# Superbot_motor_boost_mk2.net
KiCad netlist of a schematic drawn in Altium Designer
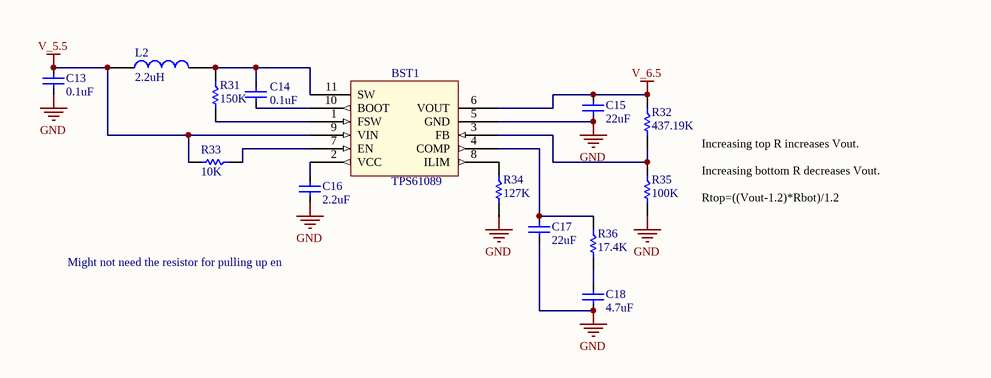
[diagram p0: Superbot_motor_boost_mk2.SchDoc]

(export (version "E")
  (design (tool "Eeschema 10.0.6"))
  (components
    (comp (ref "BST1")
      (value "TPS61089")
      (footprint "VQFN_RNR0011A_1mm")
      (description "Boost Switching Regulator IC Positive Adjustable 4.5V 1 Output 7A 11-VFQFN")
      (fields
        (field (name "MANUFACTURER") "Texas Instruments")
        (field (name "MANUFACTURER PART NUM") "TPS61089RNRT")
      )
      (libsource (lib "SuperBot_Schlib1") (part "TPS61089"))
    )
    (comp (ref "C13")
      (value "0.1uF")
      (footprint "CAP0603R")
      (description "Capacitor")
      (fields
        (field (name "MANUFACTURER") "Microchip Technology")
        (field (name "MANUFACTURER PART NUM") "MIC5378YC5-TR")
      )
      (libsource (lib "SuperBot_Schlib1") (part "C"))
    )
    (comp (ref "C14")
      (value "0.1uF")
      (footprint "CAP0603R")
      (description "Capacitor")
      (fields
        (field (name "MANUFACTURER") "Microchip Technology")
        (field (name "MANUFACTURER PART NUM") "MIC5378YC5-TR")
      )
      (libsource (lib "SuperBot_Schlib1") (part "C"))
    )
    (comp (ref "C15")
      (value "22uF")
      (footprint "CAP0805R")
      (description "Capacitor")
      (fields
        (field (name "MANUFACTURER") "Microchip Technology")
        (field (name "MANUFACTURER PART NUM") "MIC5378YC5-TR")
      )
      (libsource (lib "SuperBot_Schlib1") (part "C"))
    )
    (comp (ref "C16")
      (value "2.2uF")
      (footprint "CAP0603R")
      (description "Capacitor")
      (fields
        (field (name "MANUFACTURER") "Microchip Technology")
        (field (name "MANUFACTURER PART NUM") "MIC5378YC5-TR")
      )
      (libsource (lib "SuperBot_Schlib1") (part "C"))
    )
    (comp (ref "C17")
      (value "22uF")
      (footprint "CAP0805R")
      (description "Capacitor")
      (fields
        (field (name "MANUFACTURER") "Microchip Technology")
        (field (name "MANUFACTURER PART NUM") "MIC5378YC5-TR")
      )
      (libsource (lib "SuperBot_Schlib1") (part "C"))
    )
    (comp (ref "C18")
      (value "4.7uF")
      (footprint "CAP0603R")
      (description "Capacitor")
      (fields
        (field (name "MANUFACTURER") "Microchip Technology")
        (field (name "MANUFACTURER PART NUM") "MIC5378YC5-TR")
      )
      (libsource (lib "SuperBot_Schlib1") (part "C"))
    )
    (comp (ref "L2")
      (value "2.2uH")
      (footprint "744031004")
      (description "Inductor")
      (libsource (lib "SuperBot_Schlib1") (part "L"))
    )
    (comp (ref "R31")
      (value "150K")
      (footprint "RES0603R")
      (description "Resistor")
      (libsource (lib "SuperBot_Schlib1") (part "R"))
    )
    (comp (ref "R32")
      (value "437.19K")
      (footprint "RES0603R")
      (description "Resistor")
      (libsource (lib "SuperBot_Schlib1") (part "R"))
    )
    (comp (ref "R33")
      (value "10K")
      (footprint "RES0603R")
      (description "Resistor")
      (libsource (lib "SuperBot_Schlib1") (part "R"))
    )
    (comp (ref "R34")
      (value "127K")
      (footprint "RES0603R")
      (description "Resistor")
      (libsource (lib "SuperBot_Schlib1") (part "R"))
    )
    (comp (ref "R35")
      (value "100K")
      (footprint "RES0603R")
      (description "Resistor")
      (libsource (lib "SuperBot_Schlib1") (part "R"))
    )
    (comp (ref "R36")
      (value "17.4K")
      (footprint "RES0603R")
      (description "Resistor")
      (libsource (lib "SuperBot_Schlib1") (part "R"))
    )
  )
  (nets
    (net (code "1") (name "GND") (class "Default")
      (node (ref "BST1") (pin "5") (pinfunction "GND_5") (pintype "power_in"))
      (node (ref "C13") (pin "2") (pinfunction "2_2") (pintype "passive"))
      (node (ref "C15") (pin "2") (pinfunction "2_2") (pintype "passive"))
      (node (ref "C16") (pin "2") (pinfunction "2_2") (pintype "passive"))
      (node (ref "C17") (pin "2") (pinfunction "2_2") (pintype "passive"))
      (node (ref "C18") (pin "2") (pinfunction "2_2") (pintype "passive"))
      (node (ref "R34") (pin "2") (pintype "passive"))
      (node (ref "R35") (pin "2") (pintype "passive"))
    )
    (net (code "2") (name "Net-(BST1-BOOT)") (class "Default")
      (node (ref "BST1") (pin "10") (pinfunction "BOOT_10") (pintype "output"))
      (node (ref "C14") (pin "2") (pinfunction "2_2") (pintype "passive"))
    )
    (net (code "3") (name "Net-(BST1-COMP)") (class "Default")
      (node (ref "BST1") (pin "4") (pinfunction "COMP_4") (pintype "output"))
      (node (ref "C17") (pin "1") (pinfunction "1_1") (pintype "passive"))
      (node (ref "R36") (pin "1") (pintype "passive"))
    )
    (net (code "4") (name "Net-(BST1-EN)") (class "Default")
      (node (ref "BST1") (pin "7") (pinfunction "EN_7") (pintype "input"))
      (node (ref "R33") (pin "1") (pintype "passive"))
    )
    (net (code "5") (name "Net-(BST1-FB)") (class "Default")
      (node (ref "BST1") (pin "3") (pinfunction "FB_3") (pintype "input"))
      (node (ref "R32") (pin "2") (pintype "passive"))
      (node (ref "R35") (pin "1") (pintype "passive"))
    )
    (net (code "6") (name "Net-(BST1-FSW)") (class "Default")
      (node (ref "BST1") (pin "1") (pinfunction "FSW_1") (pintype "input"))
      (node (ref "R31") (pin "2") (pintype "passive"))
    )
    (net (code "7") (name "Net-(BST1-ILIM)") (class "Default")
      (node (ref "BST1") (pin "8") (pinfunction "ILIM_8") (pintype "output"))
      (node (ref "R34") (pin "1") (pintype "passive"))
    )
    (net (code "8") (name "Net-(BST1-SW)") (class "Default")
      (node (ref "BST1") (pin "11") (pinfunction "SW_11") (pintype "power_in"))
      (node (ref "C14") (pin "1") (pinfunction "1_1") (pintype "passive"))
      (node (ref "L2") (pin "2") (pinfunction "2_2") (pintype "passive"))
      (node (ref "R31") (pin "1") (pintype "passive"))
    )
    (net (code "9") (name "Net-(BST1-VCC)") (class "Default")
      (node (ref "BST1") (pin "2") (pinfunction "VCC_2") (pintype "output"))
      (node (ref "C16") (pin "1") (pinfunction "1_1") (pintype "passive"))
    )
    (net (code "10") (name "Net-(C18-Pad1)") (class "Default")
      (node (ref "C18") (pin "1") (pinfunction "1_1") (pintype "passive"))
      (node (ref "R36") (pin "2") (pintype "passive"))
    )
    (net (code "11") (name "V_5.5") (class "Default")
      (node (ref "BST1") (pin "9") (pinfunction "VIN_9") (pintype "input"))
      (node (ref "C13") (pin "1") (pinfunction "1_1") (pintype "passive"))
      (node (ref "L2") (pin "1") (pinfunction "1_1") (pintype "passive"))
      (node (ref "R33") (pin "2") (pintype "passive"))
    )
    (net (code "12") (name "V_6.5") (class "Default")
      (node (ref "BST1") (pin "6") (pinfunction "VOUT_6") (pintype "power_in"))
      (node (ref "C15") (pin "1") (pinfunction "1_1") (pintype "passive"))
      (node (ref "R32") (pin "1") (pintype "passive"))
    )
  )
)
